# Port_L_Output_Port.net
KiCad netlist of a schematic drawn in Altium Designer
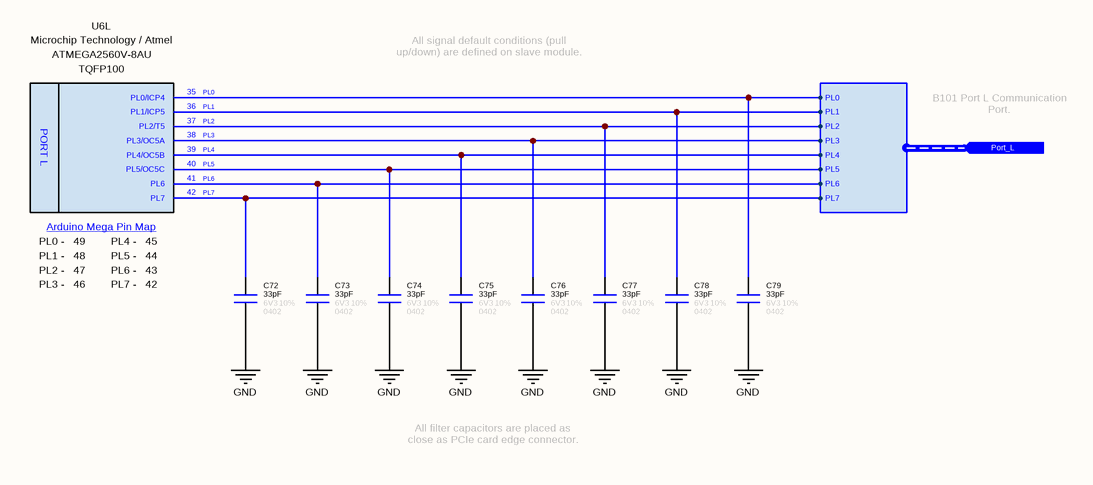
[diagram p0: Port L Output Port.SchDoc]

(export (version "E")
  (design (tool "Eeschema 10.0.6"))
  (components
    (comp (ref "C72")
      (value "33pF")
      (footprint "CAPACITOR_0402")
      (description "Capacitor - 33pF [0402] (Ceramic)")
      (fields
        (field (name "MANUFACTURER PART NUMBER") "C0402C330J9RACAUTO")
        (field (name "TOLERANCE") "10%")
        (field (name "CASE") "0402")
        (field (name "VOLTAGE") "6V3")
      )
      (libsource (lib "P101DA_Library") (part "Capacitor - 33pF [0402-6V3]"))
    )
    (comp (ref "C73")
      (value "33pF")
      (footprint "CAPACITOR_0402")
      (description "Capacitor - 33pF [0402] (Ceramic)")
      (fields
        (field (name "MANUFACTURER PART NUMBER") "C0402C330J9RACAUTO")
        (field (name "TOLERANCE") "10%")
        (field (name "CASE") "0402")
        (field (name "VOLTAGE") "6V3")
      )
      (libsource (lib "P101DA_Library") (part "Capacitor - 33pF [0402-6V3]"))
    )
    (comp (ref "C74")
      (value "33pF")
      (footprint "CAPACITOR_0402")
      (description "Capacitor - 33pF [0402] (Ceramic)")
      (fields
        (field (name "MANUFACTURER PART NUMBER") "C0402C330J9RACAUTO")
        (field (name "TOLERANCE") "10%")
        (field (name "CASE") "0402")
        (field (name "VOLTAGE") "6V3")
      )
      (libsource (lib "P101DA_Library") (part "Capacitor - 33pF [0402-6V3]"))
    )
    (comp (ref "C75")
      (value "33pF")
      (footprint "CAPACITOR_0402")
      (description "Capacitor - 33pF [0402] (Ceramic)")
      (fields
        (field (name "MANUFACTURER PART NUMBER") "C0402C330J9RACAUTO")
        (field (name "TOLERANCE") "10%")
        (field (name "CASE") "0402")
        (field (name "VOLTAGE") "6V3")
      )
      (libsource (lib "P101DA_Library") (part "Capacitor - 33pF [0402-6V3]"))
    )
    (comp (ref "C76")
      (value "33pF")
      (footprint "CAPACITOR_0402")
      (description "Capacitor - 33pF [0402] (Ceramic)")
      (fields
        (field (name "MANUFACTURER PART NUMBER") "C0402C330J9RACAUTO")
        (field (name "TOLERANCE") "10%")
        (field (name "CASE") "0402")
        (field (name "VOLTAGE") "6V3")
      )
      (libsource (lib "P101DA_Library") (part "Capacitor - 33pF [0402-6V3]"))
    )
    (comp (ref "C77")
      (value "33pF")
      (footprint "CAPACITOR_0402")
      (description "Capacitor - 33pF [0402] (Ceramic)")
      (fields
        (field (name "MANUFACTURER PART NUMBER") "C0402C330J9RACAUTO")
        (field (name "TOLERANCE") "10%")
        (field (name "CASE") "0402")
        (field (name "VOLTAGE") "6V3")
      )
      (libsource (lib "P101DA_Library") (part "Capacitor - 33pF [0402-6V3]"))
    )
    (comp (ref "C78")
      (value "33pF")
      (footprint "CAPACITOR_0402")
      (description "Capacitor - 33pF [0402] (Ceramic)")
      (fields
        (field (name "MANUFACTURER PART NUMBER") "C0402C330J9RACAUTO")
        (field (name "TOLERANCE") "10%")
        (field (name "CASE") "0402")
        (field (name "VOLTAGE") "6V3")
      )
      (libsource (lib "P101DA_Library") (part "Capacitor - 33pF [0402-6V3]"))
    )
    (comp (ref "C79")
      (value "33pF")
      (footprint "CAPACITOR_0402")
      (description "Capacitor - 33pF [0402] (Ceramic)")
      (fields
        (field (name "MANUFACTURER PART NUMBER") "C0402C330J9RACAUTO")
        (field (name "TOLERANCE") "10%")
        (field (name "CASE") "0402")
        (field (name "VOLTAGE") "6V3")
      )
      (libsource (lib "P101DA_Library") (part "Capacitor - 33pF [0402-6V3]"))
    )
    (comp (ref "U6")
      (value "ATMEGA2560V-8AU")
      (footprint "TQFP-100")
      (description "ATmega Series 256 KB Flash 8 KB SRAM 8 MHz 8-Bit Microcontroller - TQFP-100")
      (fields
        (field (name "MANUFACTURER NAME") "Microchip Technology / Atmel")
        (field (name "MANUFACTURER PART NUMBER") "ATMEGA2560V-8AU")
        (field (name "CASE") "TQFP100")
      )
      (libsource (lib "P101DA_Library") (part "IC - AtMega2560V-8AU"))
    )
  )
  (nets
    (net (code "2") (name "/PL0") (class "Default")
      (node (ref "C79") (pin "2") (pinfunction "2_2") (pintype "passive"))
      (node (ref "U6") (pin "35") (pinfunction "PL0/ICP4_35") (pintype "passive"))
    )
    (net (code "3") (name "/PL1") (class "Default")
      (node (ref "C78") (pin "2") (pinfunction "2_2") (pintype "passive"))
      (node (ref "U6") (pin "36") (pinfunction "PL1/ICP5_36") (pintype "passive"))
    )
    (net (code "4") (name "/PL2") (class "Default")
      (node (ref "C77") (pin "2") (pinfunction "2_2") (pintype "passive"))
      (node (ref "U6") (pin "37") (pinfunction "PL2/T5_37") (pintype "passive"))
    )
    (net (code "5") (name "/PL3") (class "Default")
      (node (ref "C76") (pin "2") (pinfunction "2_2") (pintype "passive"))
      (node (ref "U6") (pin "38") (pinfunction "PL3/OC5A_38") (pintype "passive"))
    )
    (net (code "6") (name "/PL4") (class "Default")
      (node (ref "C75") (pin "2") (pinfunction "2_2") (pintype "passive"))
      (node (ref "U6") (pin "39") (pinfunction "PL4/OC5B_39") (pintype "passive"))
    )
    (net (code "7") (name "/PL5") (class "Default")
      (node (ref "C74") (pin "2") (pinfunction "2_2") (pintype "passive"))
      (node (ref "U6") (pin "40") (pinfunction "PL5/OC5C_40") (pintype "passive"))
    )
    (net (code "8") (name "/PL6") (class "Default")
      (node (ref "C73") (pin "2") (pinfunction "2_2") (pintype "passive"))
      (node (ref "U6") (pin "41") (pinfunction "PL6_41") (pintype "passive"))
    )
    (net (code "9") (name "/PL7") (class "Default")
      (node (ref "C72") (pin "2") (pinfunction "2_2") (pintype "passive"))
      (node (ref "U6") (pin "42") (pinfunction "PL7_42") (pintype "passive"))
    )
    (net (code "11") (name "GND") (class "Default")
      (node (ref "C72") (pin "1") (pinfunction "1_1") (pintype "passive"))
      (node (ref "C73") (pin "1") (pinfunction "1_1") (pintype "passive"))
      (node (ref "C74") (pin "1") (pinfunction "1_1") (pintype "passive"))
      (node (ref "C75") (pin "1") (pinfunction "1_1") (pintype "passive"))
      (node (ref "C76") (pin "1") (pinfunction "1_1") (pintype "passive"))
      (node (ref "C77") (pin "1") (pinfunction "1_1") (pintype "passive"))
      (node (ref "C78") (pin "1") (pinfunction "1_1") (pintype "passive"))
      (node (ref "C79") (pin "1") (pinfunction "1_1") (pintype "passive"))
    )
  )
)
